# headphone-driver.net
KiCad netlist of a schematic drawn in EAGLE
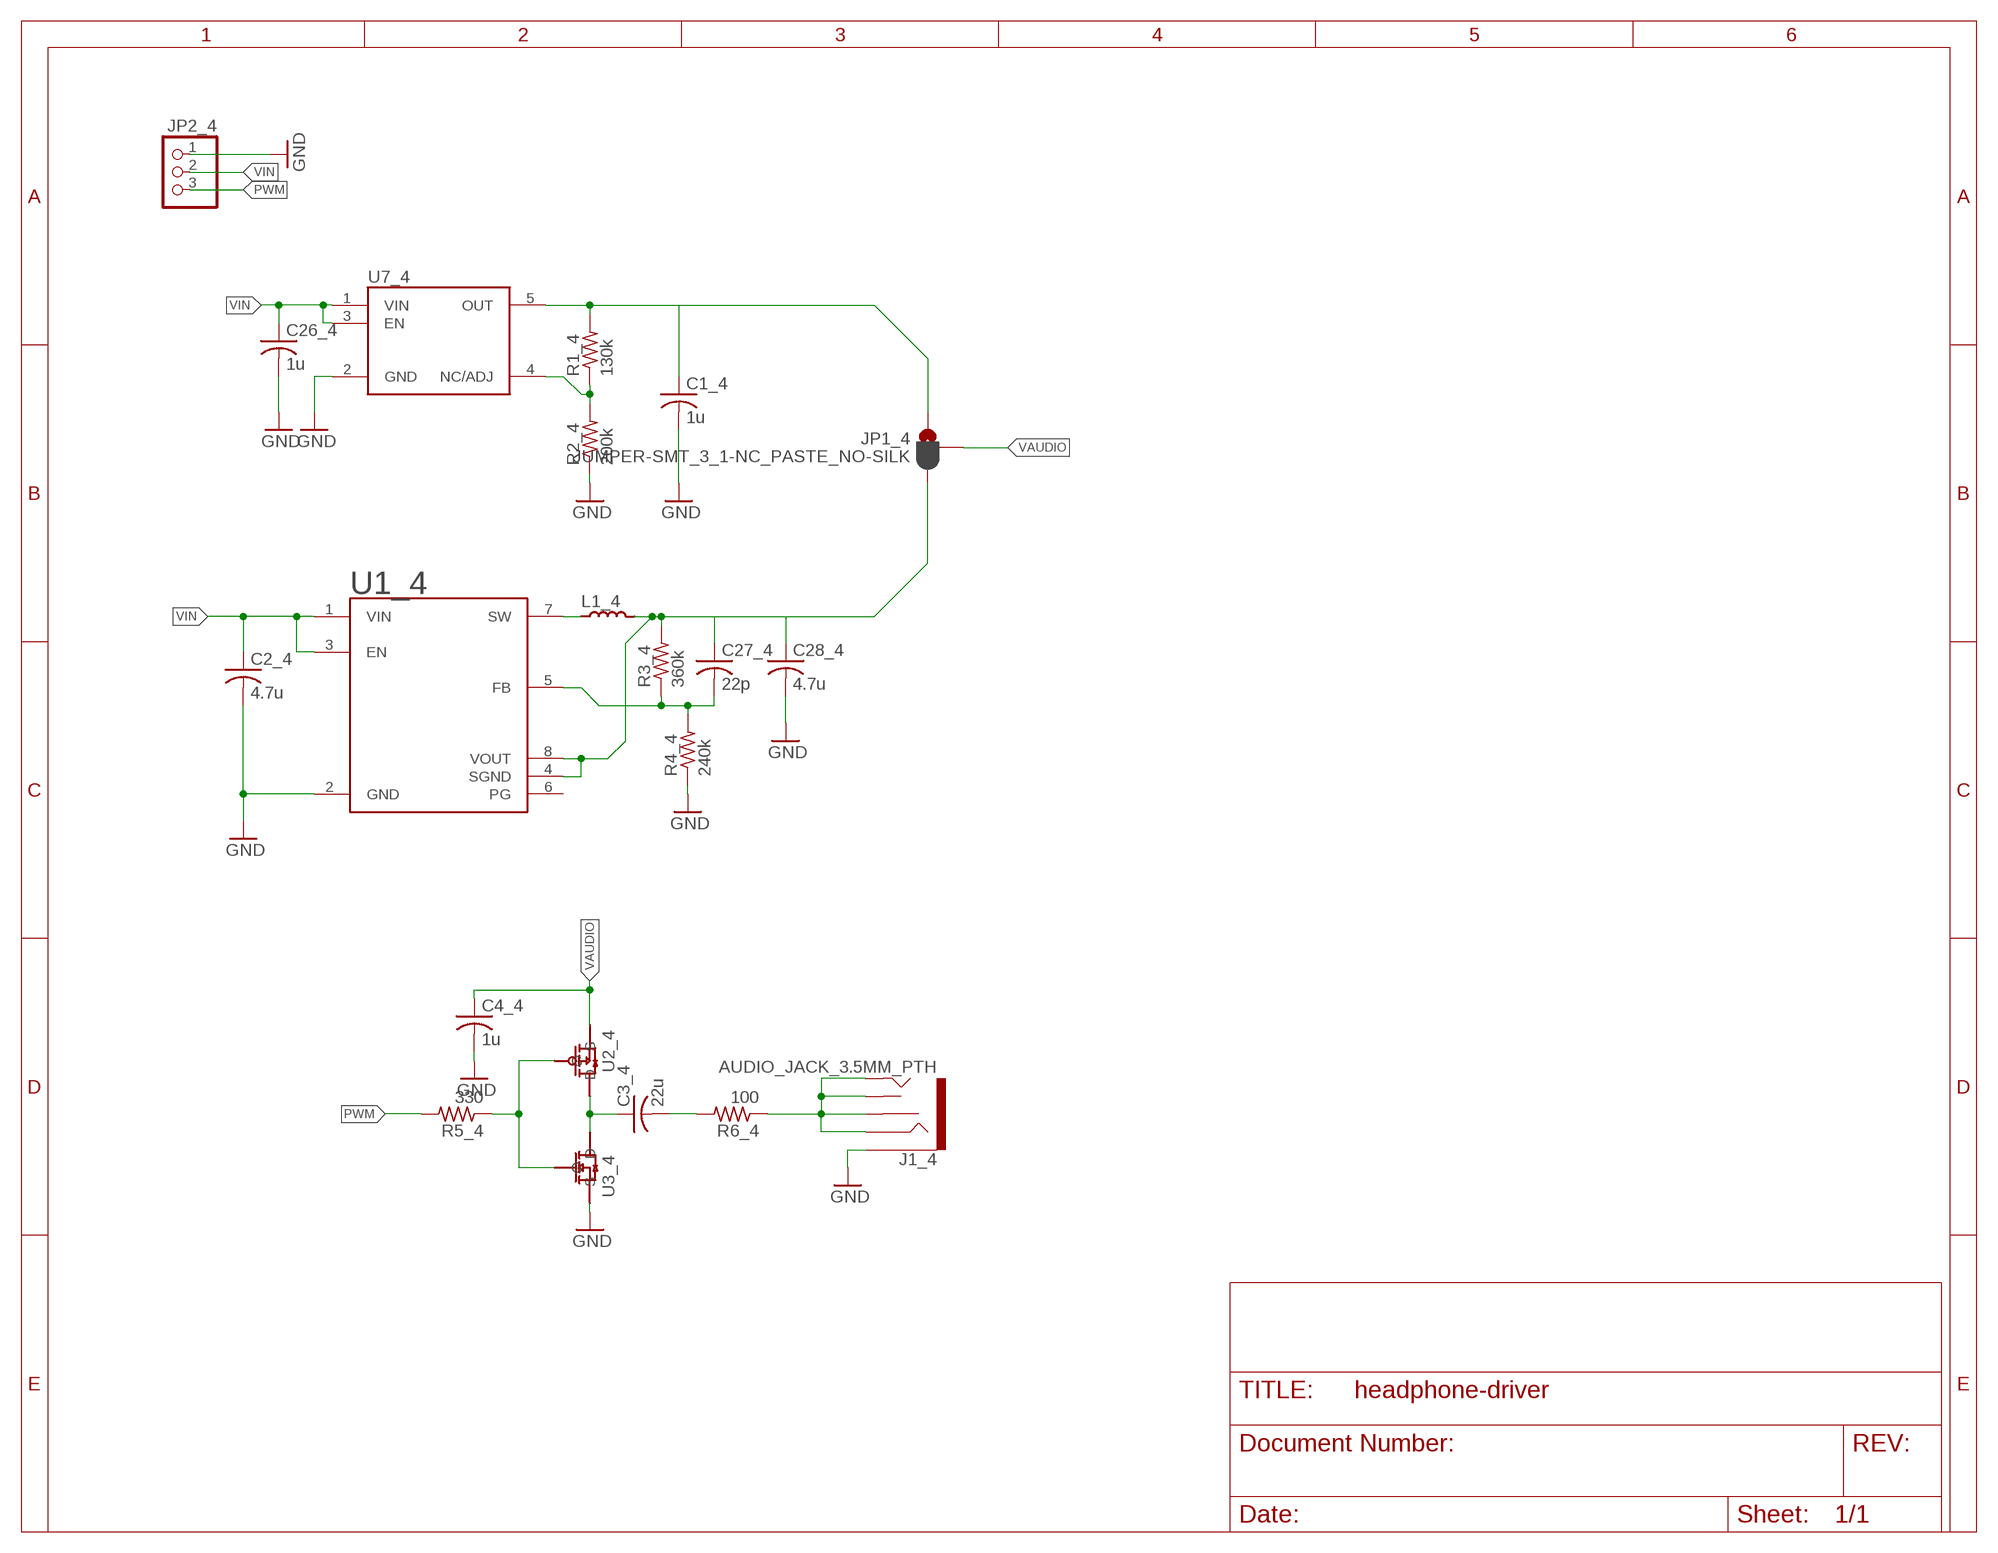
[diagram p0: schematic, sheet 1]

(export (version "E")
  (design (tool "Eeschema 10.0.6"))
  (components
    (comp (ref "C1_4")
      (value "1u")
      (footprint "eagle-import:C0603")
      (fields (field (name "MFR") "SAMSUNG"))
      (libsource (lib "eagle-import") (part "C-USC0603"))
    )
    (comp (ref "C2_4")
      (value "4.7u")
      (footprint "eagle-import:C0603")
      (fields (field (name "MFR") "SAMSUNG"))
      (libsource (lib "eagle-import") (part "C-USC0603"))
    )
    (comp (ref "C3_4")
      (value "22u")
      (footprint "eagle-import:C0805")
      (fields (field (name "MFR") "MURATA"))
      (libsource (lib "eagle-import") (part "C-USC0805"))
    )
    (comp (ref "C4_4")
      (value "1u")
      (footprint "eagle-import:C0603")
      (fields (field (name "MFR") "SAMSUNG"))
      (libsource (lib "eagle-import") (part "C-USC0603"))
    )
    (comp (ref "C26_4")
      (value "1u")
      (footprint "eagle-import:C0603")
      (fields (field (name "MFR") "SAMSUNG"))
      (libsource (lib "eagle-import") (part "C-USC0603"))
    )
    (comp (ref "C27_4")
      (value "22p")
      (footprint "eagle-import:C0402")
      (fields (field (name "MFR") "KEMET"))
      (libsource (lib "eagle-import") (part "C-USC0402"))
    )
    (comp (ref "C28_4")
      (value "4.7u")
      (footprint "eagle-import:C0603")
      (fields (field (name "MFR") "SAMSUNG"))
      (libsource (lib "eagle-import") (part "C-USC0603"))
    )
    (comp (ref "J1_4")
      (value "AUDIO_JACK_3.5MM_PTH")
      (footprint "eagle-import:AUDIO-JACK")
      (libsource (lib "eagle-import") (part "AUDIO_JACK_3.5MM_PTH"))
    )
    (comp (ref "JP1_4")
      (value "JUMPER-SMT_3_1-NC_PASTE_NO-SILK")
      (footprint "eagle-import:SMT-JUMPER_3_1-NC_PASTE_NO-SILK")
      (libsource (lib "eagle-import") (part "JUMPER-SMT_3_1-NC_PASTE_NO-SILK"))
    )
    (comp (ref "JP2_4")
      (value "PINHD-1X3")
      (footprint "eagle-import:1X03")
      (libsource (lib "eagle-import") (part "PINHD-1X3"))
    )
    (comp (ref "L1_4")
      (value "22u")
      (footprint "eagle-import:LQH3NPNXXXXMEX")
      (fields (field (name "MFR") "MURATA"))
      (libsource (lib "eagle-import") (part "LQH3NPN220MMEL"))
    )
    (comp (ref "R1_4")
      (value "130k")
      (footprint "eagle-import:R0603")
      (fields (field (name "MFR") "PANASONIC"))
      (libsource (lib "eagle-import") (part "R-US_R0603"))
    )
    (comp (ref "R2_4")
      (value "200k")
      (footprint "eagle-import:R0603")
      (fields (field (name "MFR") "PANASONIC"))
      (libsource (lib "eagle-import") (part "R-US_R0603"))
    )
    (comp (ref "R3_4")
      (value "360k")
      (footprint "eagle-import:R0603")
      (fields (field (name "MFR") "PANASONIC"))
      (libsource (lib "eagle-import") (part "R-US_R0603"))
    )
    (comp (ref "R4_4")
      (value "240k")
      (footprint "eagle-import:R0603")
      (fields (field (name "MFR") "PANASONIC"))
      (libsource (lib "eagle-import") (part "R-US_R0603"))
    )
    (comp (ref "R5_4")
      (value "330")
      (footprint "eagle-import:R0603")
      (fields (field (name "MFR") "YAGEO"))
      (libsource (lib "eagle-import") (part "R-US_R0603"))
    )
    (comp (ref "R6_4")
      (value "100")
      (footprint "eagle-import:R0603")
      (fields (field (name "MFR") "YAGEO"))
      (libsource (lib "eagle-import") (part "R-US_R0603"))
    )
    (comp (ref "U1_4")
      (value "TPS62120")
      (footprint "eagle-import:SOP65P280X145-8N")
      (fields (field (name "MFR") "TI"))
      (libsource (lib "eagle-import") (part "TPS62120"))
    )
    (comp (ref "U2_4")
      (value "TP2104K1-G")
      (footprint "eagle-import:TP2104K1-G")
      (fields (field (name "MFR") "MICROCHIP"))
      (libsource (lib "eagle-import") (part "TP2104K1-G"))
    )
    (comp (ref "U3_4")
      (value "TN2106K1-G")
      (footprint "eagle-import:TN2106K1-G")
      (fields (field (name "MFR") "MICROCHIP"))
      (libsource (lib "eagle-import") (part "TN2106K1-G"))
    )
    (comp (ref "U7_4")
      (value "MIC5225")
      (footprint "eagle-import:MIC5225")
      (fields (field (name "MFR") "MICROCHIP"))
      (libsource (lib "eagle-import") (part "MIC5225"))
    )
  )
  (nets
    (net (code "1") (name "GND") (class "Default")
      (node (ref "C1_4") (pin "2") (pinfunction "2_2") (pintype "passive"))
      (node (ref "C26_4") (pin "2") (pinfunction "2_2") (pintype "passive"))
      (node (ref "C28_4") (pin "2") (pinfunction "2_2") (pintype "passive"))
      (node (ref "C2_4") (pin "2") (pinfunction "2_2") (pintype "passive"))
      (node (ref "C4_4") (pin "2") (pinfunction "2_2") (pintype "passive"))
      (node (ref "J1_4") (pin "SLEEVE") (pinfunction "SLEEVE_SLEEVE") (pintype "bidirectional"))
      (node (ref "JP2_4") (pin "1") (pinfunction "1_1") (pintype "passive"))
      (node (ref "R2_4") (pin "1") (pinfunction "1_1") (pintype "passive"))
      (node (ref "R4_4") (pin "1") (pinfunction "1_1") (pintype "passive"))
      (node (ref "U1_4") (pin "2") (pinfunction "GND_2") (pintype "bidirectional"))
      (node (ref "U3_4") (pin "S") (pinfunction "S_S") (pintype "bidirectional"))
      (node (ref "U7_4") (pin "2") (pinfunction "GND_2") (pintype "bidirectional"))
    )
    (net (code "2") (name "Net-(C3_4-Pad1)") (class "Default")
      (node (ref "C3_4") (pin "1") (pinfunction "1_1") (pintype "passive"))
      (node (ref "U2_4") (pin "D") (pinfunction "D_D") (pintype "bidirectional"))
      (node (ref "U3_4") (pin "D") (pinfunction "D_D") (pintype "bidirectional"))
    )
    (net (code "3") (name "Net-(C3_4-Pad2)") (class "Default")
      (node (ref "C3_4") (pin "2") (pinfunction "2_2") (pintype "passive"))
      (node (ref "R6_4") (pin "2") (pinfunction "2_2") (pintype "passive"))
    )
    (net (code "4") (name "Net-(J1_4-PadRING)") (class "Default")
      (node (ref "J1_4") (pin "RING") (pinfunction "RING_RING") (pintype "bidirectional"))
      (node (ref "J1_4") (pin "RSH") (pinfunction "RSH_RSH") (pintype "bidirectional"))
      (node (ref "J1_4") (pin "TIP") (pinfunction "TIP_TIP") (pintype "bidirectional"))
      (node (ref "J1_4") (pin "TSH") (pinfunction "TSH_TSH") (pintype "bidirectional"))
      (node (ref "R6_4") (pin "1") (pinfunction "1_1") (pintype "passive"))
    )
    (net (code "5") (name "Net-(R5_4-Pad1)") (class "Default")
      (node (ref "R5_4") (pin "1") (pinfunction "1_1") (pintype "passive"))
      (node (ref "U2_4") (pin "G") (pinfunction "G_G") (pintype "bidirectional"))
      (node (ref "U3_4") (pin "G") (pinfunction "G_G") (pintype "bidirectional"))
    )
    (net (code "6") (name "Net-(U1_4-FB)") (class "Default")
      (node (ref "C27_4") (pin "2") (pinfunction "2_2") (pintype "passive"))
      (node (ref "R3_4") (pin "1") (pinfunction "1_1") (pintype "passive"))
      (node (ref "R4_4") (pin "2") (pinfunction "2_2") (pintype "passive"))
      (node (ref "U1_4") (pin "5") (pinfunction "FB_5") (pintype "bidirectional"))
    )
    (net (code "7") (name "Net-(U1_4-SGND)") (class "Default")
      (node (ref "C27_4") (pin "1") (pinfunction "1_1") (pintype "passive"))
      (node (ref "C28_4") (pin "1") (pinfunction "1_1") (pintype "passive"))
      (node (ref "JP1_4") (pin "3") (pinfunction "3_3") (pintype "passive"))
      (node (ref "L1_4") (pin "P$2") (pinfunction "P$2_P$2") (pintype "bidirectional"))
      (node (ref "R3_4") (pin "2") (pinfunction "2_2") (pintype "passive"))
      (node (ref "U1_4") (pin "4") (pinfunction "SGND_4") (pintype "bidirectional"))
      (node (ref "U1_4") (pin "8") (pinfunction "VOUT_8") (pintype "bidirectional"))
    )
    (net (code "8") (name "Net-(U1_4-SW)") (class "Default")
      (node (ref "L1_4") (pin "P$1") (pinfunction "P$1_P$1") (pintype "bidirectional"))
      (node (ref "U1_4") (pin "7") (pinfunction "SW_7") (pintype "bidirectional"))
    )
    (net (code "9") (name "Net-(U7_4-NC{slash}ADJ)") (class "Default")
      (node (ref "R1_4") (pin "1") (pinfunction "1_1") (pintype "passive"))
      (node (ref "R2_4") (pin "2") (pinfunction "2_2") (pintype "passive"))
      (node (ref "U7_4") (pin "4") (pinfunction "NC/ADJ_4") (pintype "bidirectional"))
    )
    (net (code "10") (name "Net-(U7_4-OUT)") (class "Default")
      (node (ref "C1_4") (pin "1") (pinfunction "1_1") (pintype "passive"))
      (node (ref "JP1_4") (pin "1") (pinfunction "1_1") (pintype "passive"))
      (node (ref "R1_4") (pin "2") (pinfunction "2_2") (pintype "passive"))
      (node (ref "U7_4") (pin "5") (pinfunction "OUT_5") (pintype "bidirectional"))
    )
    (net (code "11") (name "PWM") (class "Default")
      (node (ref "JP2_4") (pin "3") (pinfunction "3_3") (pintype "passive"))
      (node (ref "R5_4") (pin "2") (pinfunction "2_2") (pintype "passive"))
    )
    (net (code "12") (name "VAUDIO") (class "Default")
      (node (ref "C4_4") (pin "1") (pinfunction "1_1") (pintype "passive"))
      (node (ref "JP1_4") (pin "2") (pinfunction "2_2") (pintype "passive"))
      (node (ref "U2_4") (pin "S") (pinfunction "S_S") (pintype "bidirectional"))
    )
    (net (code "13") (name "VIN") (class "Default")
      (node (ref "C26_4") (pin "1") (pinfunction "1_1") (pintype "passive"))
      (node (ref "C2_4") (pin "1") (pinfunction "1_1") (pintype "passive"))
      (node (ref "JP2_4") (pin "2") (pinfunction "2_2") (pintype "passive"))
      (node (ref "U1_4") (pin "1") (pinfunction "VIN_1") (pintype "bidirectional"))
      (node (ref "U1_4") (pin "3") (pinfunction "EN_3") (pintype "bidirectional"))
      (node (ref "U7_4") (pin "1") (pinfunction "VIN_1") (pintype "bidirectional"))
      (node (ref "U7_4") (pin "3") (pinfunction "EN_3") (pintype "bidirectional"))
    )
    (net (code "14") (name "unconnected-(U1_4-PG-Pad6)") (class "Default")
      (node (ref "U1_4") (pin "6") (pinfunction "PG_6") (pintype "bidirectional"))
    )
  )
)
